# Output.net
KiCad netlist of a schematic drawn in EAGLE
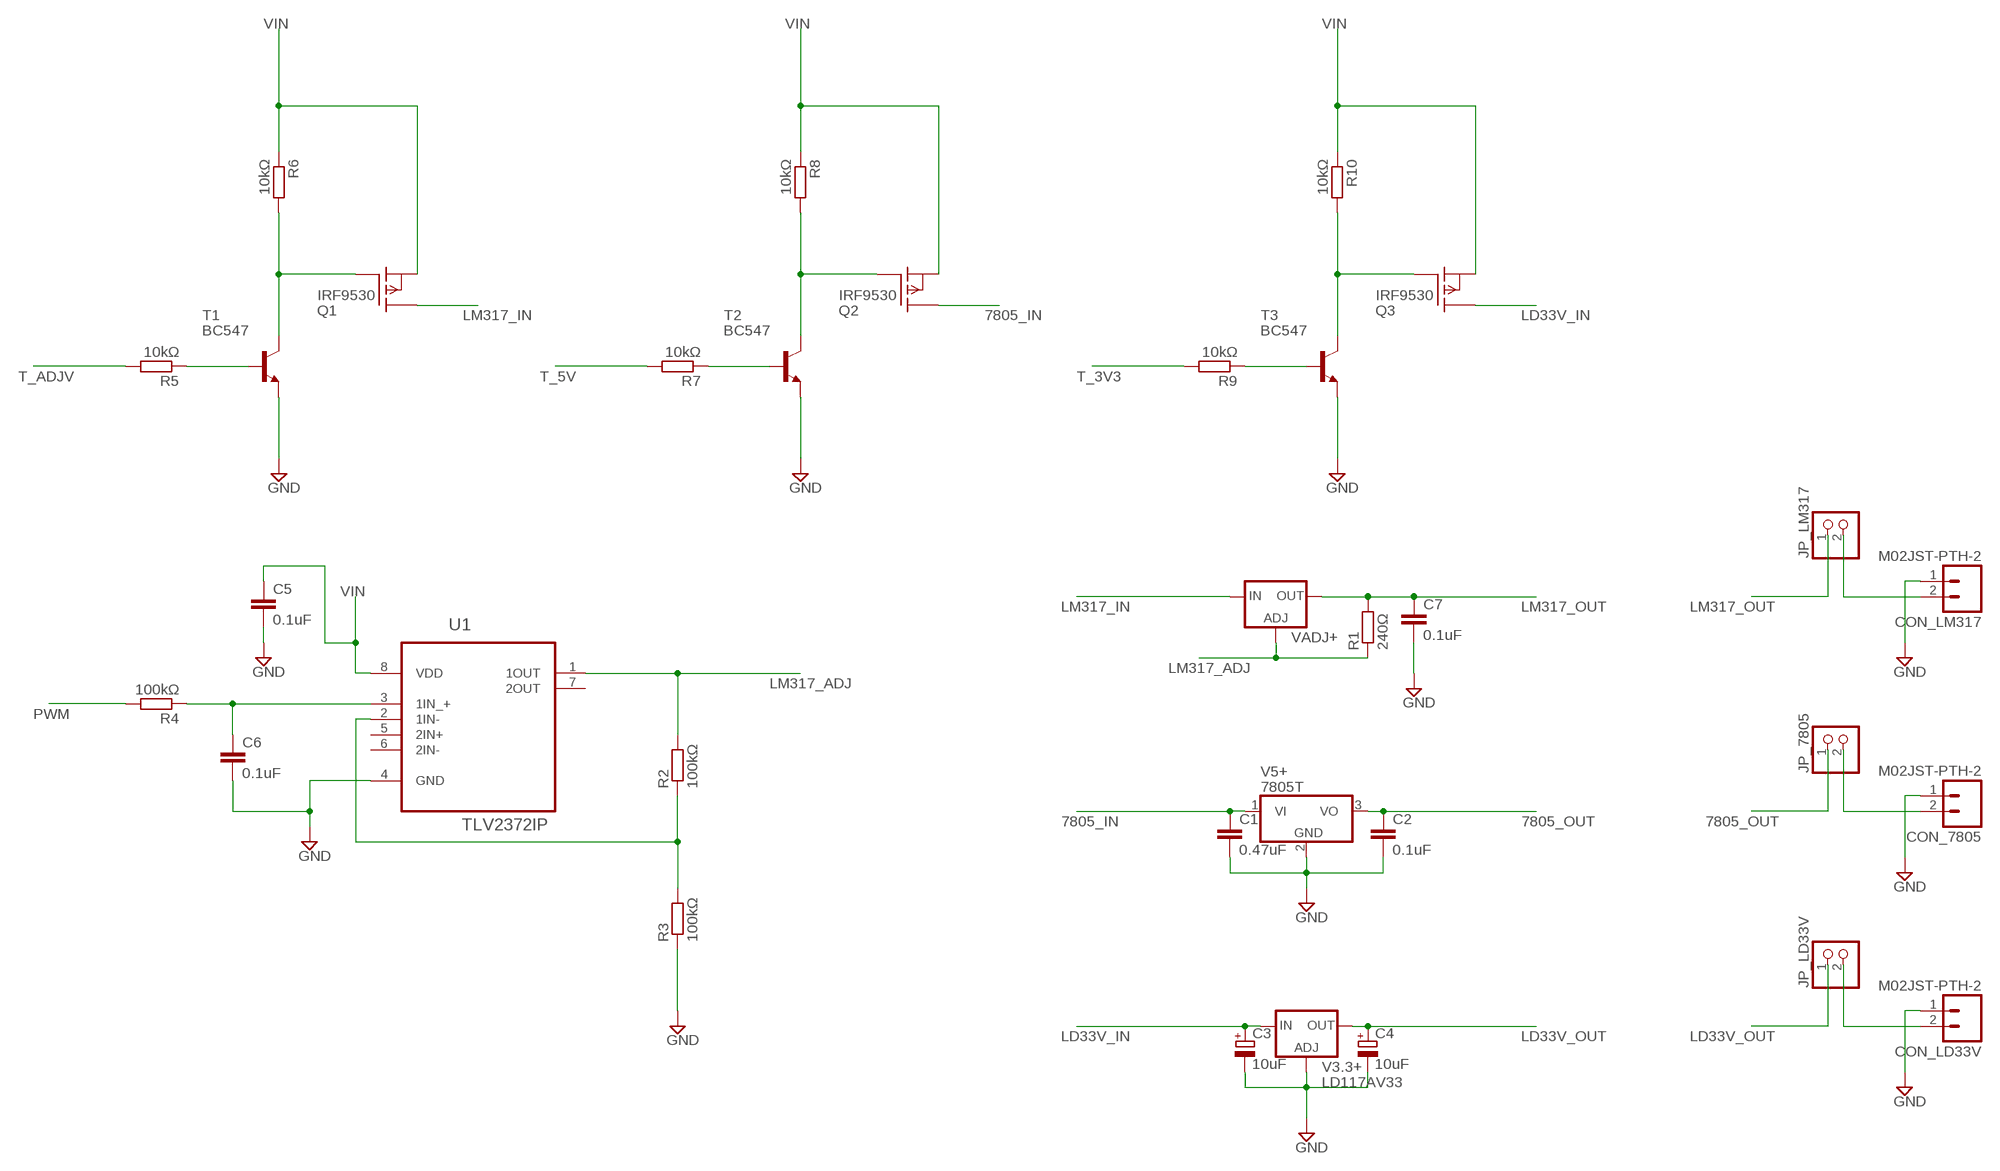
[diagram p0: schematic, sheet 1]

(export (version "E")
  (design (tool "Eeschema 10.0.6"))
  (components
    (comp (ref "C1")
      (value "0.47uF")
      (footprint "eagle-import:C025-025X050")
      (libsource (lib "eagle-import") (part "C-EU025-025X050"))
    )
    (comp (ref "C2")
      (value "0.1uF")
      (footprint "eagle-import:C025-025X050")
      (libsource (lib "eagle-import") (part "C-EU025-025X050"))
    )
    (comp (ref "C3")
      (value "10uF")
      (footprint "eagle-import:E2,5-6")
      (libsource (lib "eagle-import") (part "CPOL-EUE2.5-6"))
    )
    (comp (ref "C4")
      (value "10uF")
      (footprint "eagle-import:E2,5-6")
      (libsource (lib "eagle-import") (part "CPOL-EUE2.5-6"))
    )
    (comp (ref "C5")
      (value "0.1uF")
      (footprint "eagle-import:C025-025X050")
      (libsource (lib "eagle-import") (part "C-EU025-025X050"))
    )
    (comp (ref "C6")
      (value "0.1uF")
      (footprint "eagle-import:C025-025X050")
      (libsource (lib "eagle-import") (part "C-EU025-025X050"))
    )
    (comp (ref "C7")
      (value "0.1uF")
      (footprint "eagle-import:C025-025X050")
      (libsource (lib "eagle-import") (part "C-EU025-025X050"))
    )
    (comp (ref "CON_7805")
      (value "M02JST-PTH-2")
      (footprint "eagle-import:JST-2-PTH")
      (libsource (lib "eagle-import") (part "M02JST-PTH-2"))
    )
    (comp (ref "CON_LD33V")
      (value "M02JST-PTH-2")
      (footprint "eagle-import:JST-2-PTH")
      (libsource (lib "eagle-import") (part "M02JST-PTH-2"))
    )
    (comp (ref "CON_LM317")
      (value "M02JST-PTH-2")
      (footprint "eagle-import:JST-2-PTH")
      (libsource (lib "eagle-import") (part "M02JST-PTH-2"))
    )
    (comp (ref "JP_7805")
      (value "PINHD-1X2")
      (footprint "eagle-import:1X02")
      (libsource (lib "eagle-import") (part "PINHD-1X2"))
    )
    (comp (ref "JP_LD33V")
      (value "PINHD-1X2")
      (footprint "eagle-import:1X02")
      (libsource (lib "eagle-import") (part "PINHD-1X2"))
    )
    (comp (ref "JP_LM317")
      (value "PINHD-1X2")
      (footprint "eagle-import:1X02")
      (libsource (lib "eagle-import") (part "PINHD-1X2"))
    )
    (comp (ref "Q1")
      (value "IRF9530")
      (footprint "eagle-import:TO220")
      (libsource (lib "eagle-import") (part "IRF9530"))
    )
    (comp (ref "Q2")
      (value "IRF9530")
      (footprint "eagle-import:TO220")
      (libsource (lib "eagle-import") (part "IRF9530"))
    )
    (comp (ref "Q3")
      (value "IRF9530")
      (footprint "eagle-import:TO220")
      (libsource (lib "eagle-import") (part "IRF9530"))
    )
    (comp (ref "R1")
      (value "240Ω")
      (footprint "eagle-import:0207_10")
      (libsource (lib "eagle-import") (part "R-EU_0207/10"))
    )
    (comp (ref "R2")
      (value "100kΩ")
      (footprint "eagle-import:0207_10")
      (libsource (lib "eagle-import") (part "R-EU_0207/10"))
    )
    (comp (ref "R3")
      (value "100kΩ")
      (footprint "eagle-import:0207_10")
      (libsource (lib "eagle-import") (part "R-EU_0207/10"))
    )
    (comp (ref "R4")
      (value "100kΩ")
      (footprint "eagle-import:0207_10")
      (libsource (lib "eagle-import") (part "R-EU_0207/10"))
    )
    (comp (ref "R5")
      (value "10kΩ")
      (footprint "eagle-import:0207_10")
      (libsource (lib "eagle-import") (part "R-EU_0207/10"))
    )
    (comp (ref "R6")
      (value "10kΩ")
      (footprint "eagle-import:0207_10")
      (libsource (lib "eagle-import") (part "R-EU_0207/10"))
    )
    (comp (ref "R7")
      (value "10kΩ")
      (footprint "eagle-import:0207_10")
      (libsource (lib "eagle-import") (part "R-EU_0207/10"))
    )
    (comp (ref "R8")
      (value "10kΩ")
      (footprint "eagle-import:0207_10")
      (libsource (lib "eagle-import") (part "R-EU_0207/10"))
    )
    (comp (ref "R9")
      (value "10kΩ")
      (footprint "eagle-import:0207_10")
      (libsource (lib "eagle-import") (part "R-EU_0207/10"))
    )
    (comp (ref "R10")
      (value "10kΩ")
      (footprint "eagle-import:0207_10")
      (libsource (lib "eagle-import") (part "R-EU_0207/10"))
    )
    (comp (ref "T1")
      (value "BC547")
      (footprint "eagle-import:TO92")
      (libsource (lib "eagle-import") (part "BC547"))
    )
    (comp (ref "T2")
      (value "BC547")
      (footprint "eagle-import:TO92")
      (libsource (lib "eagle-import") (part "BC547"))
    )
    (comp (ref "T3")
      (value "BC547")
      (footprint "eagle-import:TO92")
      (libsource (lib "eagle-import") (part "BC547"))
    )
    (comp (ref "U1")
      (value "TLV2372IP")
      (footprint "eagle-import:DIP254P762X508-8")
      (libsource (lib "eagle-import") (part "TLV2372IP"))
    )
    (comp (ref "V3.3+")
      (value "LD117AV33")
      (footprint "eagle-import:TO220L1")
      (libsource (lib "eagle-import") (part "LD117A?V33"))
    )
    (comp (ref "V5+")
      (value "7805T")
      (footprint "eagle-import:TO220H")
      (libsource (lib "eagle-import") (part "78T05"))
    )
    (comp (ref "VADJ+")
      (value "LM317TL")
      (footprint "eagle-import:317TL")
      (libsource (lib "eagle-import") (part "LM317TL"))
    )
  )
  (nets
    (net (code "1") (name "/7805_IN") (class "Default")
      (node (ref "C1") (pin "1") (pinfunction "1_1") (pintype "passive"))
      (node (ref "Q2") (pin "2") (pinfunction "D_2") (pintype "passive"))
      (node (ref "V5+") (pin "1") (pinfunction "VI_1") (pintype "input"))
    )
    (net (code "2") (name "/7805_OUT") (class "Default")
      (node (ref "C2") (pin "1") (pinfunction "1_1") (pintype "passive"))
      (node (ref "JP_7805") (pin "1") (pinfunction "1_1") (pintype "passive"))
      (node (ref "V5+") (pin "3") (pinfunction "VO_3") (pintype "passive"))
    )
    (net (code "3") (name "/LD33V_IN") (class "Default")
      (node (ref "C3") (pin "+") (pinfunction "+_+") (pintype "passive"))
      (node (ref "Q3") (pin "2") (pinfunction "D_2") (pintype "passive"))
      (node (ref "V3.3+") (pin "3") (pinfunction "IN_3") (pintype "input"))
    )
    (net (code "4") (name "/LD33V_OUT") (class "Default")
      (node (ref "C4") (pin "+") (pinfunction "+_+") (pintype "passive"))
      (node (ref "JP_LD33V") (pin "1") (pinfunction "1_1") (pintype "passive"))
      (node (ref "V3.3+") (pin "2") (pinfunction "OUT_2") (pintype "passive"))
    )
    (net (code "5") (name "/LM317_ADJ") (class "Default")
      (node (ref "R1") (pin "1") (pinfunction "1_1") (pintype "passive"))
      (node (ref "R2") (pin "2") (pinfunction "2_2") (pintype "passive"))
      (node (ref "U1") (pin "1") (pinfunction "1OUT_1") (pintype "output"))
      (node (ref "VADJ+") (pin "1") (pinfunction "ADJ_1") (pintype "input"))
    )
    (net (code "6") (name "/LM317_IN") (class "Default")
      (node (ref "Q1") (pin "2") (pinfunction "D_2") (pintype "passive"))
      (node (ref "VADJ+") (pin "3") (pinfunction "IN_3") (pintype "input"))
    )
    (net (code "7") (name "/LM317_OUT") (class "Default")
      (node (ref "C7") (pin "1") (pinfunction "1_1") (pintype "passive"))
      (node (ref "JP_LM317") (pin "1") (pinfunction "1_1") (pintype "passive"))
      (node (ref "R1") (pin "2") (pinfunction "2_2") (pintype "passive"))
      (node (ref "VADJ+") (pin "2") (pinfunction "OUT_2") (pintype "passive"))
    )
    (net (code "8") (name "/PWM") (class "Default")
      (node (ref "R4") (pin "2") (pinfunction "2_2") (pintype "passive"))
    )
    (net (code "9") (name "/T_3V3") (class "Default")
      (node (ref "R9") (pin "2") (pinfunction "2_2") (pintype "passive"))
    )
    (net (code "10") (name "/T_5V") (class "Default")
      (node (ref "R7") (pin "2") (pinfunction "2_2") (pintype "passive"))
    )
    (net (code "11") (name "/T_ADJV") (class "Default")
      (node (ref "R5") (pin "2") (pinfunction "2_2") (pintype "passive"))
    )
    (net (code "12") (name "/VIN") (class "Default")
      (node (ref "C5") (pin "1") (pinfunction "1_1") (pintype "passive"))
      (node (ref "Q1") (pin "3") (pinfunction "S_3") (pintype "passive"))
      (node (ref "Q2") (pin "3") (pinfunction "S_3") (pintype "passive"))
      (node (ref "Q3") (pin "3") (pinfunction "S_3") (pintype "passive"))
      (node (ref "R10") (pin "1") (pinfunction "1_1") (pintype "passive"))
      (node (ref "R6") (pin "1") (pinfunction "1_1") (pintype "passive"))
      (node (ref "R8") (pin "1") (pinfunction "1_1") (pintype "passive"))
      (node (ref "U1") (pin "8") (pinfunction "VDD_8") (pintype "power_in"))
    )
    (net (code "13") (name "GND") (class "Default")
      (node (ref "C1") (pin "2") (pinfunction "2_2") (pintype "passive"))
      (node (ref "C2") (pin "2") (pinfunction "2_2") (pintype "passive"))
      (node (ref "C3") (pin "-") (pinfunction "-_-") (pintype "passive"))
      (node (ref "C4") (pin "-") (pinfunction "-_-") (pintype "passive"))
      (node (ref "C5") (pin "2") (pinfunction "2_2") (pintype "passive"))
      (node (ref "C6") (pin "2") (pinfunction "2_2") (pintype "passive"))
      (node (ref "C7") (pin "2") (pinfunction "2_2") (pintype "passive"))
      (node (ref "CON_7805") (pin "1") (pinfunction "1_1") (pintype "passive"))
      (node (ref "CON_LD33V") (pin "1") (pinfunction "1_1") (pintype "passive"))
      (node (ref "CON_LM317") (pin "1") (pinfunction "1_1") (pintype "passive"))
      (node (ref "R3") (pin "1") (pinfunction "1_1") (pintype "passive"))
      (node (ref "T1") (pin "1") (pinfunction "E_1") (pintype "passive"))
      (node (ref "T2") (pin "1") (pinfunction "E_1") (pintype "passive"))
      (node (ref "T3") (pin "1") (pinfunction "E_1") (pintype "passive"))
      (node (ref "U1") (pin "4") (pinfunction "GND_4") (pintype "passive"))
      (node (ref "V3.3+") (pin "1") (pinfunction "ADJ_1") (pintype "input"))
      (node (ref "V5+") (pin "2") (pinfunction "GND_2") (pintype "passive"))
    )
    (net (code "14") (name "Net-(CON_7805-Pad2)") (class "Default")
      (node (ref "CON_7805") (pin "2") (pinfunction "2_2") (pintype "passive"))
      (node (ref "JP_7805") (pin "2") (pinfunction "2_2") (pintype "passive"))
    )
    (net (code "15") (name "Net-(CON_LD33V-Pad2)") (class "Default")
      (node (ref "CON_LD33V") (pin "2") (pinfunction "2_2") (pintype "passive"))
      (node (ref "JP_LD33V") (pin "2") (pinfunction "2_2") (pintype "passive"))
    )
    (net (code "16") (name "Net-(CON_LM317-Pad2)") (class "Default")
      (node (ref "CON_LM317") (pin "2") (pinfunction "2_2") (pintype "passive"))
      (node (ref "JP_LM317") (pin "2") (pinfunction "2_2") (pintype "passive"))
    )
    (net (code "17") (name "Net-(Q1-G)") (class "Default")
      (node (ref "Q1") (pin "1") (pinfunction "G_1") (pintype "passive"))
      (node (ref "R6") (pin "2") (pinfunction "2_2") (pintype "passive"))
      (node (ref "T1") (pin "3") (pinfunction "C_3") (pintype "passive"))
    )
    (net (code "18") (name "Net-(Q2-G)") (class "Default")
      (node (ref "Q2") (pin "1") (pinfunction "G_1") (pintype "passive"))
      (node (ref "R8") (pin "2") (pinfunction "2_2") (pintype "passive"))
      (node (ref "T2") (pin "3") (pinfunction "C_3") (pintype "passive"))
    )
    (net (code "19") (name "Net-(Q3-G)") (class "Default")
      (node (ref "Q3") (pin "1") (pinfunction "G_1") (pintype "passive"))
      (node (ref "R10") (pin "2") (pinfunction "2_2") (pintype "passive"))
      (node (ref "T3") (pin "3") (pinfunction "C_3") (pintype "passive"))
    )
    (net (code "20") (name "Net-(T1-B)") (class "Default")
      (node (ref "R5") (pin "1") (pinfunction "1_1") (pintype "passive"))
      (node (ref "T1") (pin "2") (pinfunction "B_2") (pintype "passive"))
    )
    (net (code "21") (name "Net-(T2-B)") (class "Default")
      (node (ref "R7") (pin "1") (pinfunction "1_1") (pintype "passive"))
      (node (ref "T2") (pin "2") (pinfunction "B_2") (pintype "passive"))
    )
    (net (code "22") (name "Net-(T3-B)") (class "Default")
      (node (ref "R9") (pin "1") (pinfunction "1_1") (pintype "passive"))
      (node (ref "T3") (pin "2") (pinfunction "B_2") (pintype "passive"))
    )
    (net (code "23") (name "Net-(U1-1IN-)") (class "Default")
      (node (ref "R2") (pin "1") (pinfunction "1_1") (pintype "passive"))
      (node (ref "R3") (pin "2") (pinfunction "2_2") (pintype "passive"))
      (node (ref "U1") (pin "2") (pinfunction "1IN-_2") (pintype "input"))
    )
    (net (code "24") (name "Net-(U1-1IN_+)") (class "Default")
      (node (ref "C6") (pin "1") (pinfunction "1_1") (pintype "passive"))
      (node (ref "R4") (pin "1") (pinfunction "1_1") (pintype "passive"))
      (node (ref "U1") (pin "3") (pinfunction "1IN_+_3") (pintype "input"))
    )
    (net (code "25") (name "unconnected-(U1-2IN+-Pad5)") (class "Default")
      (node (ref "U1") (pin "5") (pinfunction "2IN+_5") (pintype "input"))
    )
    (net (code "26") (name "unconnected-(U1-2IN--Pad6)") (class "Default")
      (node (ref "U1") (pin "6") (pinfunction "2IN-_6") (pintype "input"))
    )
    (net (code "27") (name "unconnected-(U1-2OUT-Pad7)") (class "Default")
      (node (ref "U1") (pin "7") (pinfunction "2OUT_7") (pintype "output"))
    )
  )
)
